# ToF-Module.net
KiCad netlist of a schematic drawn in EAGLE
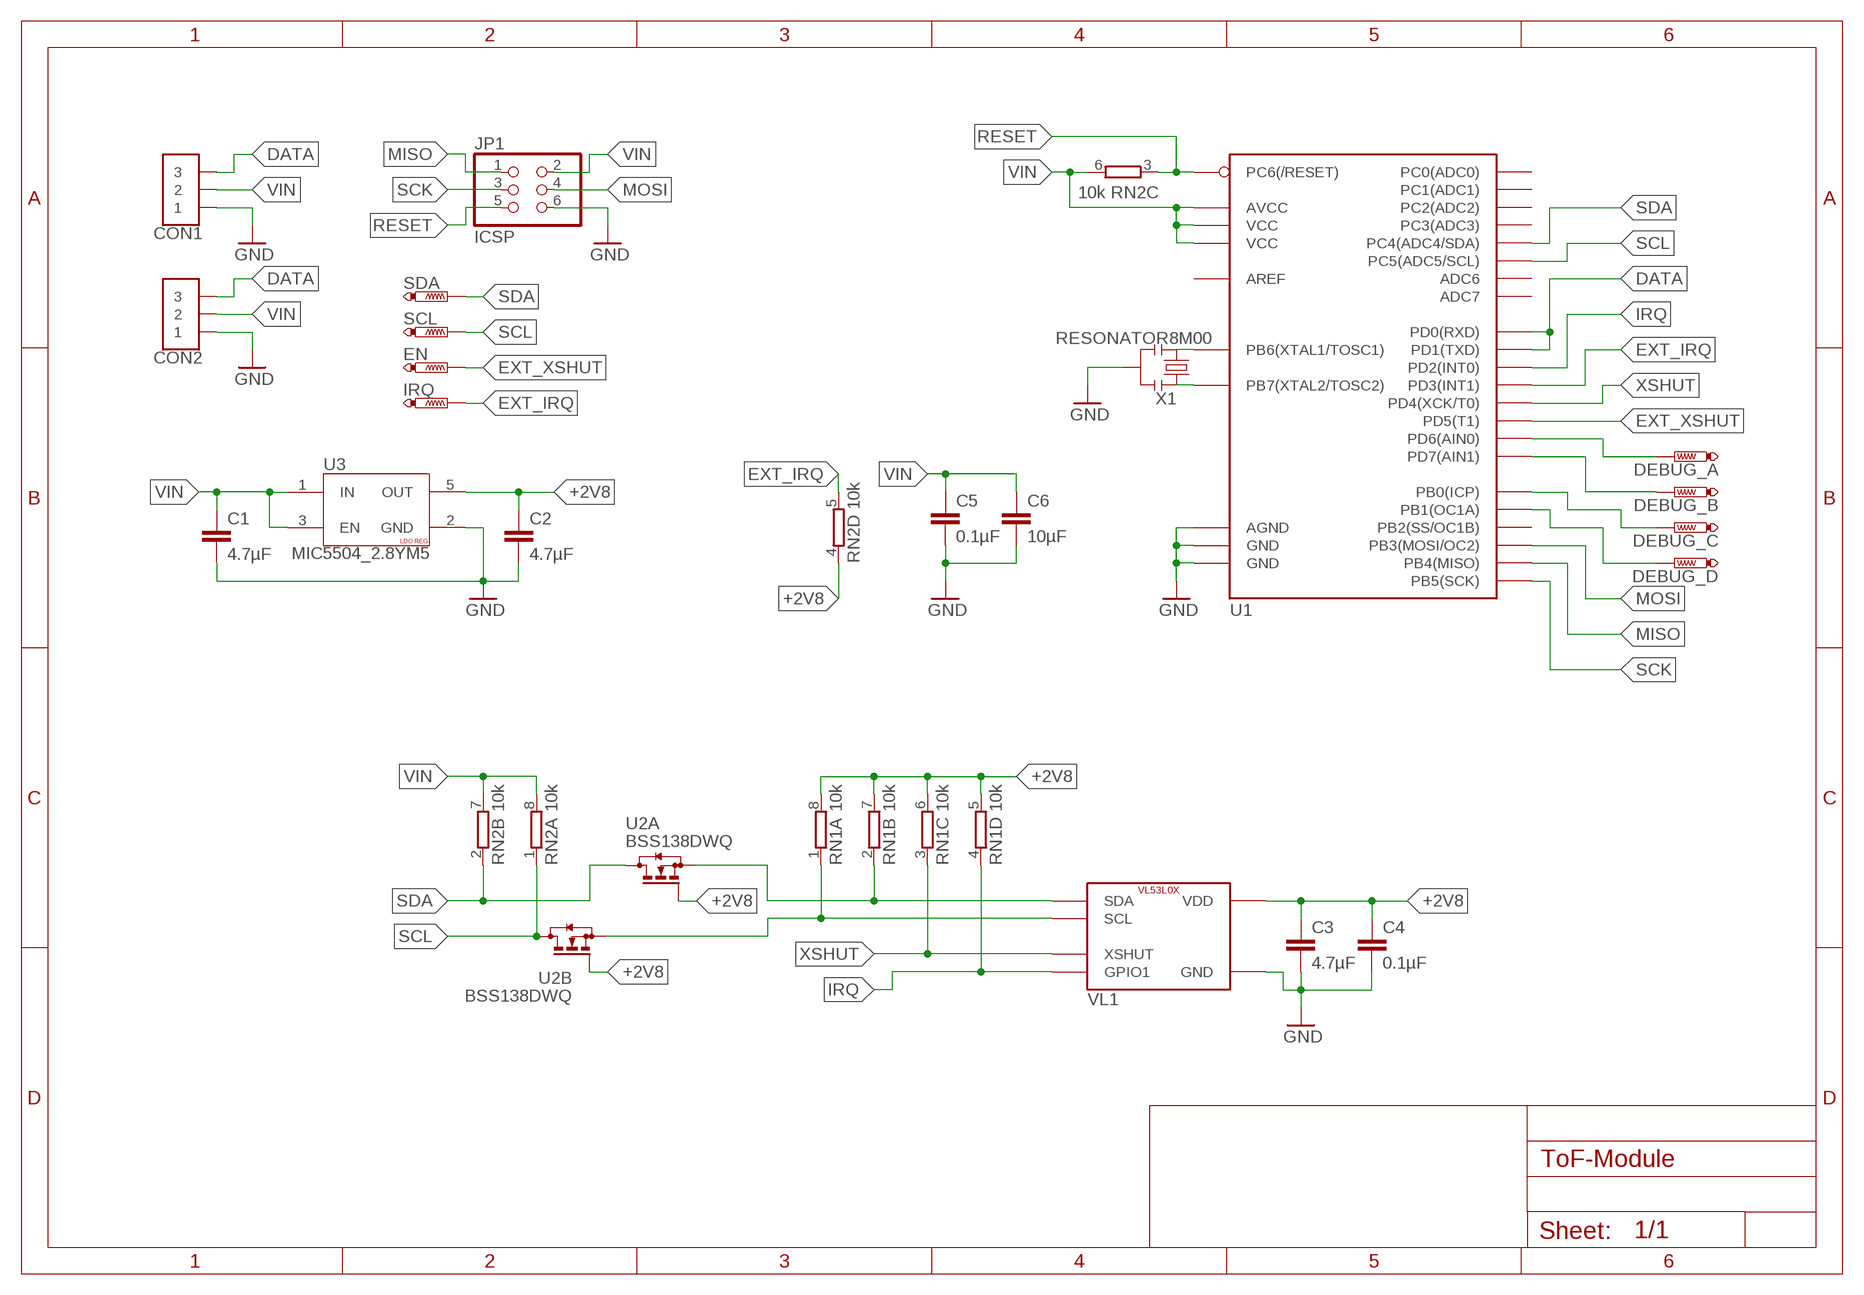
[diagram p0: schematic, sheet 1]

(export (version "E")
  (design (tool "Eeschema 10.0.6"))
  (components
    (comp (ref "C1")
      (value "4.7µF")
      (footprint "eagle-import:C0603")
      (libsource (lib "eagle-import") (part "C-EUC0603"))
    )
    (comp (ref "C2")
      (value "4.7µF")
      (footprint "eagle-import:C0603")
      (libsource (lib "eagle-import") (part "C-EUC0603"))
    )
    (comp (ref "C3")
      (value "4.7µF")
      (footprint "eagle-import:C0603")
      (libsource (lib "eagle-import") (part "C-EUC0603"))
    )
    (comp (ref "C4")
      (value "0.1µF")
      (footprint "eagle-import:C0603")
      (libsource (lib "eagle-import") (part "C-EUC0603"))
    )
    (comp (ref "C5")
      (value "0.1µF")
      (footprint "eagle-import:C0603")
      (libsource (lib "eagle-import") (part "C-EUC0603"))
    )
    (comp (ref "C6")
      (value "10µF")
      (footprint "eagle-import:C0805")
      (libsource (lib "eagle-import") (part "C-EUC0805"))
    )
    (comp (ref "CON1")
      (value "JST-03")
      (footprint "eagle-import:GH-03-V")
      (libsource (lib "eagle-import") (part "JST-03"))
    )
    (comp (ref "CON2")
      (value "JST-03")
      (footprint "eagle-import:GH-03-V")
      (libsource (lib "eagle-import") (part "JST-03"))
    )
    (comp (ref "DEBUG_A")
      (value "PTR1TP15R")
      (footprint "eagle-import:TP15R")
      (libsource (lib "eagle-import") (part "PTR1TP15R"))
    )
    (comp (ref "DEBUG_B")
      (value "PTR1TP15R")
      (footprint "eagle-import:TP15R")
      (libsource (lib "eagle-import") (part "PTR1TP15R"))
    )
    (comp (ref "DEBUG_C")
      (value "PTR1TP15R")
      (footprint "eagle-import:TP15R")
      (libsource (lib "eagle-import") (part "PTR1TP15R"))
    )
    (comp (ref "DEBUG_D")
      (value "PTR1TP15R")
      (footprint "eagle-import:TP15R")
      (libsource (lib "eagle-import") (part "PTR1TP15R"))
    )
    (comp (ref "EN")
      (value "PTR1TP20SQ")
      (footprint "eagle-import:TP20SQ")
      (libsource (lib "eagle-import") (part "PTR1TP20SQ"))
    )
    (comp (ref "IRQ")
      (value "PTR1TP20SQ")
      (footprint "eagle-import:TP20SQ")
      (libsource (lib "eagle-import") (part "PTR1TP20SQ"))
    )
    (comp (ref "JP1")
      (value "ICSP")
      (footprint "eagle-import:2X03")
      (libsource (lib "eagle-import") (part "PINHD-2X3"))
    )
    (comp (ref "RN1")
      (value "10k")
      (footprint "eagle-import:CAT16")
      (fields
        (field (name "MANF") "CAT16-103J4LF")
        (field (name "MOUSER") "652-CAT16-103J4LF")
        (field (name "RS") "522-5412")
      )
      (libsource (lib "eagle-import") (part "4R-NCAT16"))
    )
    (comp (ref "RN2")
      (value "10k")
      (footprint "eagle-import:CAT16")
      (fields
        (field (name "MANF") "CAT16-103J4LF")
        (field (name "MOUSER") "652-CAT16-103J4LF")
        (field (name "RS") "522-5412")
      )
      (libsource (lib "eagle-import") (part "4R-NCAT16"))
    )
    (comp (ref "SCL")
      (value "PTR1TP20SQ")
      (footprint "eagle-import:TP20SQ")
      (libsource (lib "eagle-import") (part "PTR1TP20SQ"))
    )
    (comp (ref "SDA")
      (value "PTR1TP20SQ")
      (footprint "eagle-import:TP20SQ")
      (libsource (lib "eagle-import") (part "PTR1TP20SQ"))
    )
    (comp (ref "U1")
      (value "ATMEGA328P")
      (footprint "eagle-import:QFP80P900X900X120-32")
      (fields (field (name "MANF") "ATMEGA328P-AU"))
      (libsource (lib "eagle-import") (part "ATMEGA328P"))
    )
    (comp (ref "U2")
      (value "BSS138DWQ")
      (footprint "eagle-import:SOT65P210X110-6")
      (fields (field (name "MANF") "BSS138DWQ-7"))
      (libsource (lib "eagle-import") (part "BSS138DWQ"))
    )
    (comp (ref "U3")
      (value "MIC5504_2.8YM5")
      (footprint "eagle-import:SOT95P280X145-5")
      (fields (field (name "MANF") "MIC5504-2.8YM5-TR"))
      (libsource (lib "eagle-import") (part "MIC5504_2.8YM5"))
    )
    (comp (ref "VL1")
      (value "VL53L0X")
      (footprint "eagle-import:VL53L0X")
      (fields (field (name "MANF") "VL53L0CXV0DH/1"))
      (libsource (lib "eagle-import") (part "VL53L0X"))
    )
    (comp (ref "X1")
      (value "RESONATOR8M00")
      (footprint "eagle-import:CSTNE")
      (fields (field (name "MANF") "CSTNE8M00"))
      (libsource (lib "eagle-import") (part "RESONATOR8M00"))
    )
  )
  (nets
    (net (code "1") (name "+2V8") (class "Default")
      (node (ref "C2") (pin "1") (pinfunction "1_1") (pintype "passive"))
      (node (ref "C3") (pin "1") (pinfunction "1_1") (pintype "passive"))
      (node (ref "C4") (pin "1") (pinfunction "1_1") (pintype "passive"))
      (node (ref "RN1") (pin "5") (pinfunction "2_5") (pintype "passive"))
      (node (ref "RN1") (pin "6") (pinfunction "2_6") (pintype "passive"))
      (node (ref "RN1") (pin "7") (pinfunction "2_7") (pintype "passive"))
      (node (ref "RN1") (pin "8") (pinfunction "2_8") (pintype "passive"))
      (node (ref "RN2") (pin "4") (pinfunction "1_4") (pintype "passive"))
      (node (ref "U2") (pin "G1") (pinfunction "G_G1") (pintype "passive"))
      (node (ref "U2") (pin "G2") (pinfunction "G_G2") (pintype "passive"))
      (node (ref "U3") (pin "5") (pinfunction "OUT_5") (pintype "bidirectional"))
      (node (ref "VL1") (pin "1") (pinfunction "VDD_1") (pintype "bidirectional"))
      (node (ref "VL1") (pin "11") (pinfunction "VDD_11") (pintype "bidirectional"))
    )
    (net (code "2") (name "DATA") (class "Default")
      (node (ref "CON1") (pin "3") (pinfunction "3_3") (pintype "bidirectional"))
      (node (ref "CON2") (pin "3") (pinfunction "3_3") (pintype "bidirectional"))
      (node (ref "U1") (pin "30") (pinfunction "PD0(RXD)_30") (pintype "bidirectional"))
      (node (ref "U1") (pin "31") (pinfunction "PD1(TXD)_31") (pintype "bidirectional"))
    )
    (net (code "3") (name "EXT_IRQ") (class "Default")
      (node (ref "IRQ") (pin "TP") (pinfunction "TP_TP") (pintype "input"))
      (node (ref "RN2") (pin "5") (pinfunction "2_5") (pintype "passive"))
      (node (ref "U1") (pin "1") (pinfunction "PD3(INT1)_1") (pintype "bidirectional"))
    )
    (net (code "4") (name "EXT_XSHUT") (class "Default")
      (node (ref "EN") (pin "TP") (pinfunction "TP_TP") (pintype "input"))
      (node (ref "U1") (pin "9") (pinfunction "PD5(T1)_9") (pintype "bidirectional"))
    )
    (net (code "5") (name "GND") (class "Default")
      (node (ref "C1") (pin "2") (pinfunction "2_2") (pintype "passive"))
      (node (ref "C2") (pin "2") (pinfunction "2_2") (pintype "passive"))
      (node (ref "C3") (pin "2") (pinfunction "2_2") (pintype "passive"))
      (node (ref "C4") (pin "2") (pinfunction "2_2") (pintype "passive"))
      (node (ref "C5") (pin "2") (pinfunction "2_2") (pintype "passive"))
      (node (ref "C6") (pin "2") (pinfunction "2_2") (pintype "passive"))
      (node (ref "CON1") (pin "1") (pinfunction "1_1") (pintype "bidirectional"))
      (node (ref "CON2") (pin "1") (pinfunction "1_1") (pintype "bidirectional"))
      (node (ref "JP1") (pin "6") (pinfunction "6_6") (pintype "passive"))
      (node (ref "U1") (pin "21") (pinfunction "GND_21") (pintype "bidirectional"))
      (node (ref "U1") (pin "3") (pinfunction "GND_3") (pintype "bidirectional"))
      (node (ref "U1") (pin "5") (pinfunction "AGND_5") (pintype "bidirectional"))
      (node (ref "U3") (pin "2") (pinfunction "GND_2") (pintype "bidirectional"))
      (node (ref "VL1") (pin "12") (pinfunction "GND_12") (pintype "bidirectional"))
      (node (ref "VL1") (pin "2") (pinfunction "GND_2") (pintype "bidirectional"))
      (node (ref "VL1") (pin "3") (pinfunction "GND_3") (pintype "bidirectional"))
      (node (ref "VL1") (pin "4") (pinfunction "GND_4") (pintype "bidirectional"))
      (node (ref "VL1") (pin "6") (pinfunction "GND_6") (pintype "bidirectional"))
      (node (ref "X1") (pin "2") (pinfunction "2_2") (pintype "passive"))
    )
    (net (code "6") (name "IRQ") (class "Default")
      (node (ref "RN1") (pin "4") (pinfunction "1_4") (pintype "passive"))
      (node (ref "U1") (pin "32") (pinfunction "PD2(INT0)_32") (pintype "bidirectional"))
      (node (ref "VL1") (pin "7") (pinfunction "GPIO1_7") (pintype "bidirectional"))
    )
    (net (code "7") (name "MISO") (class "Default")
      (node (ref "JP1") (pin "1") (pinfunction "1_1") (pintype "passive"))
      (node (ref "U1") (pin "16") (pinfunction "PB4(MISO)_16") (pintype "bidirectional"))
    )
    (net (code "8") (name "MOSI") (class "Default")
      (node (ref "JP1") (pin "4") (pinfunction "4_4") (pintype "passive"))
      (node (ref "U1") (pin "15") (pinfunction "PB3(MOSI/OC2)_15") (pintype "bidirectional"))
    )
    (net (code "9") (name "Net-(RN1B-1)") (class "Default")
      (node (ref "RN1") (pin "2") (pinfunction "1_2") (pintype "passive"))
      (node (ref "U2") (pin "S1") (pinfunction "S_S1") (pintype "passive"))
      (node (ref "VL1") (pin "9") (pinfunction "SDA_9") (pintype "bidirectional"))
    )
    (net (code "10") (name "Net-(U1-PB0(ICP))") (class "Default")
      (node (ref "DEBUG_C") (pin "TP") (pinfunction "TP_TP") (pintype "input"))
      (node (ref "U1") (pin "12") (pinfunction "PB0(ICP)_12") (pintype "bidirectional"))
    )
    (net (code "11") (name "Net-(U1-PB1(OC1A))") (class "Default")
      (node (ref "DEBUG_D") (pin "TP") (pinfunction "TP_TP") (pintype "input"))
      (node (ref "U1") (pin "13") (pinfunction "PB1(OC1A)_13") (pintype "bidirectional"))
    )
    (net (code "12") (name "Net-(U1-PB6(XTAL1{slash}TOSC1))") (class "Default")
      (node (ref "U1") (pin "7") (pinfunction "PB6(XTAL1/TOSC1)_7") (pintype "bidirectional"))
      (node (ref "X1") (pin "1") (pinfunction "1_1") (pintype "passive"))
    )
    (net (code "13") (name "Net-(U1-PB7(XTAL2{slash}TOSC2))") (class "Default")
      (node (ref "U1") (pin "8") (pinfunction "PB7(XTAL2/TOSC2)_8") (pintype "bidirectional"))
      (node (ref "X1") (pin "3") (pinfunction "3_3") (pintype "passive"))
    )
    (net (code "14") (name "Net-(U1-PD6(AIN0))") (class "Default")
      (node (ref "DEBUG_A") (pin "TP") (pinfunction "TP_TP") (pintype "input"))
      (node (ref "U1") (pin "10") (pinfunction "PD6(AIN0)_10") (pintype "bidirectional"))
    )
    (net (code "15") (name "Net-(U1-PD7(AIN1))") (class "Default")
      (node (ref "DEBUG_B") (pin "TP") (pinfunction "TP_TP") (pintype "input"))
      (node (ref "U1") (pin "11") (pinfunction "PD7(AIN1)_11") (pintype "bidirectional"))
    )
    (net (code "16") (name "Net-(U2B-S)") (class "Default")
      (node (ref "RN1") (pin "1") (pinfunction "1_1") (pintype "passive"))
      (node (ref "U2") (pin "S2") (pinfunction "S_S2") (pintype "passive"))
      (node (ref "VL1") (pin "10") (pinfunction "SCL_10") (pintype "bidirectional"))
    )
    (net (code "17") (name "RESET") (class "Default")
      (node (ref "JP1") (pin "5") (pinfunction "5_5") (pintype "passive"))
      (node (ref "RN2") (pin "3") (pinfunction "1_3") (pintype "passive"))
      (node (ref "U1") (pin "29") (pinfunction "PC6(/RESET)_29") (pintype "bidirectional"))
    )
    (net (code "18") (name "SCK") (class "Default")
      (node (ref "JP1") (pin "3") (pinfunction "3_3") (pintype "passive"))
      (node (ref "U1") (pin "17") (pinfunction "PB5(SCK)_17") (pintype "bidirectional"))
    )
    (net (code "19") (name "SCL") (class "Default")
      (node (ref "RN2") (pin "1") (pinfunction "1_1") (pintype "passive"))
      (node (ref "SCL") (pin "TP") (pinfunction "TP_TP") (pintype "input"))
      (node (ref "U1") (pin "28") (pinfunction "PC5(ADC5/SCL)_28") (pintype "bidirectional"))
      (node (ref "U2") (pin "D2") (pinfunction "D_D2") (pintype "passive"))
    )
    (net (code "20") (name "SDA") (class "Default")
      (node (ref "RN2") (pin "2") (pinfunction "1_2") (pintype "passive"))
      (node (ref "SDA") (pin "TP") (pinfunction "TP_TP") (pintype "input"))
      (node (ref "U1") (pin "27") (pinfunction "PC4(ADC4/SDA)_27") (pintype "bidirectional"))
      (node (ref "U2") (pin "D1") (pinfunction "D_D1") (pintype "passive"))
    )
    (net (code "21") (name "VIN") (class "Default")
      (node (ref "C1") (pin "1") (pinfunction "1_1") (pintype "passive"))
      (node (ref "C5") (pin "1") (pinfunction "1_1") (pintype "passive"))
      (node (ref "C6") (pin "1") (pinfunction "1_1") (pintype "passive"))
      (node (ref "CON1") (pin "2") (pinfunction "2_2") (pintype "bidirectional"))
      (node (ref "CON2") (pin "2") (pinfunction "2_2") (pintype "bidirectional"))
      (node (ref "JP1") (pin "2") (pinfunction "2_2") (pintype "passive"))
      (node (ref "RN2") (pin "6") (pinfunction "2_6") (pintype "passive"))
      (node (ref "RN2") (pin "7") (pinfunction "2_7") (pintype "passive"))
      (node (ref "RN2") (pin "8") (pinfunction "2_8") (pintype "passive"))
      (node (ref "U1") (pin "18") (pinfunction "AVCC_18") (pintype "bidirectional"))
      (node (ref "U1") (pin "4") (pinfunction "VCC_4") (pintype "bidirectional"))
      (node (ref "U1") (pin "6") (pinfunction "VCC_6") (pintype "bidirectional"))
      (node (ref "U3") (pin "1") (pinfunction "IN_1") (pintype "bidirectional"))
      (node (ref "U3") (pin "3") (pinfunction "EN_3") (pintype "bidirectional"))
    )
    (net (code "22") (name "XSHUT") (class "Default")
      (node (ref "RN1") (pin "3") (pinfunction "1_3") (pintype "passive"))
      (node (ref "U1") (pin "2") (pinfunction "PD4(XCK/T0)_2") (pintype "bidirectional"))
      (node (ref "VL1") (pin "5") (pinfunction "XSHUT_5") (pintype "bidirectional"))
    )
    (net (code "23") (name "unconnected-(U1-ADC6-Pad19)") (class "Default")
      (node (ref "U1") (pin "19") (pinfunction "ADC6_19") (pintype "bidirectional"))
    )
    (net (code "24") (name "unconnected-(U1-ADC7-Pad22)") (class "Default")
      (node (ref "U1") (pin "22") (pinfunction "ADC7_22") (pintype "bidirectional"))
    )
    (net (code "25") (name "unconnected-(U1-AREF-Pad20)") (class "Default")
      (node (ref "U1") (pin "20") (pinfunction "AREF_20") (pintype "bidirectional"))
    )
    (net (code "26") (name "unconnected-(U1-PB2(SS{slash}OC1B)-Pad14)") (class "Default")
      (node (ref "U1") (pin "14") (pinfunction "PB2(SS/OC1B)_14") (pintype "bidirectional"))
    )
    (net (code "27") (name "unconnected-(U1-PC0(ADC0)-Pad23)") (class "Default")
      (node (ref "U1") (pin "23") (pinfunction "PC0(ADC0)_23") (pintype "bidirectional"))
    )
    (net (code "28") (name "unconnected-(U1-PC1(ADC1)-Pad24)") (class "Default")
      (node (ref "U1") (pin "24") (pinfunction "PC1(ADC1)_24") (pintype "bidirectional"))
    )
    (net (code "29") (name "unconnected-(U1-PC2(ADC2)-Pad25)") (class "Default")
      (node (ref "U1") (pin "25") (pinfunction "PC2(ADC2)_25") (pintype "bidirectional"))
    )
    (net (code "30") (name "unconnected-(U1-PC3(ADC3)-Pad26)") (class "Default")
      (node (ref "U1") (pin "26") (pinfunction "PC3(ADC3)_26") (pintype "bidirectional"))
    )
  )
)
